# Adapter-RJ45-SignalHead.net
KiCad netlist of a schematic drawn in EAGLE
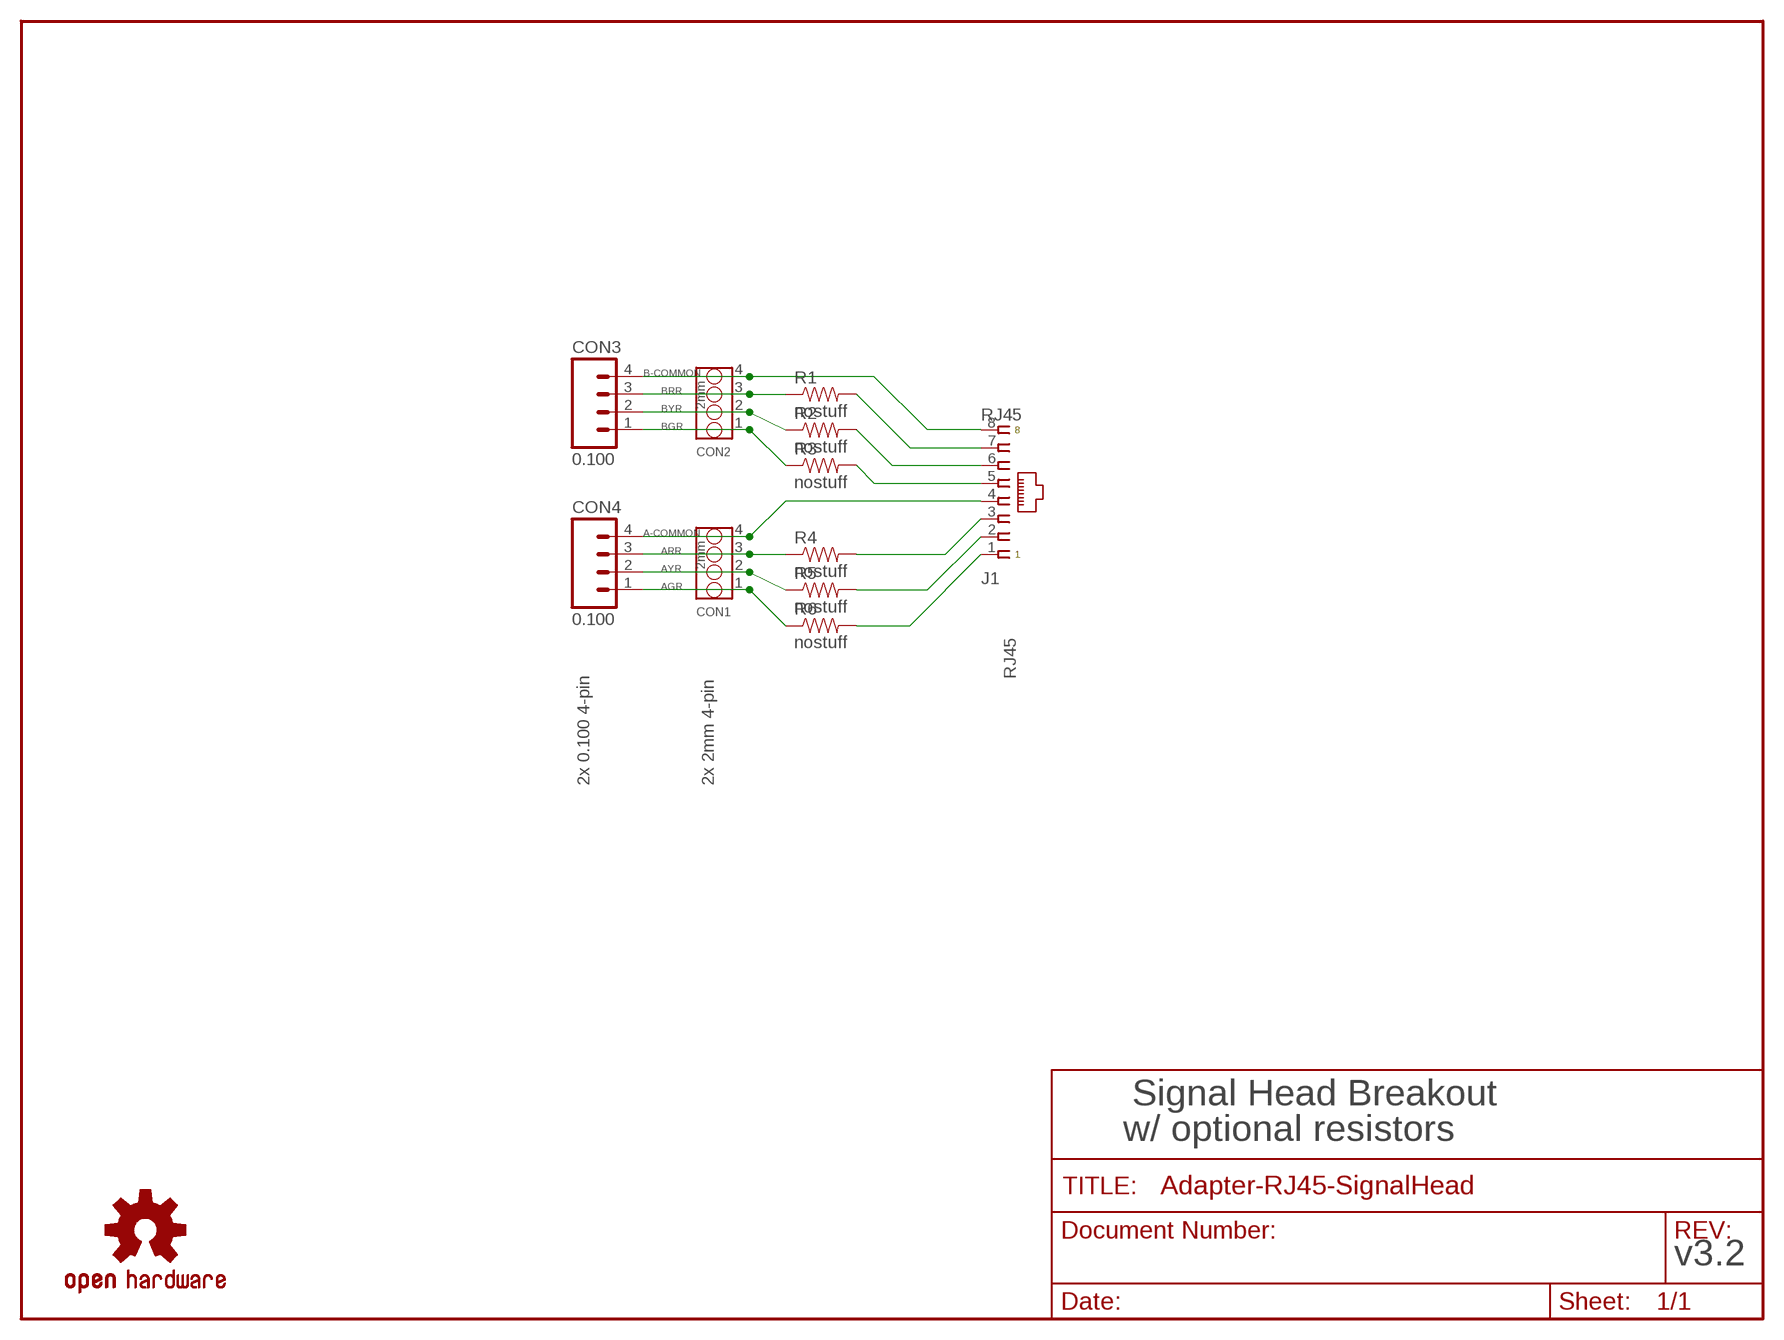
[diagram p0: schematic, sheet 1]

(export (version "E")
  (design (tool "Eeschema 10.0.6"))
  (components
    (comp (ref "CON1")
      (value "2mm")
      (footprint "eagle-import:4P-2.0")
      (libsource (lib "eagle-import") (part "CONNECTOR-GROVE-4P-2.0-3470130P1"))
    )
    (comp (ref "CON2")
      (value "2mm")
      (footprint "eagle-import:4P-2.0")
      (libsource (lib "eagle-import") (part "CONNECTOR-GROVE-4P-2.0-3470130P1"))
    )
    (comp (ref "CON3")
      (value "0.100")
      (footprint "eagle-import:1X04_LOCK")
      (libsource (lib "eagle-import") (part "CONNECTOR-M04LOCK"))
    )
    (comp (ref "CON4")
      (value "0.100")
      (footprint "eagle-import:1X04_LOCK")
      (libsource (lib "eagle-import") (part "CONNECTOR-M04LOCK"))
    )
    (comp (ref "J1")
      (value "RJ45")
      (footprint "eagle-import:RJ45-NO-SHIELD")
      (libsource (lib "eagle-import") (part "CONNECTOR-RJ45-FRONT"))
    )
    (comp (ref "R1")
      (value "nostuff")
      (footprint "eagle-import:CUT-R")
      (libsource (lib "eagle-import") (part "RPTH-R0"))
    )
    (comp (ref "R2")
      (value "nostuff")
      (footprint "eagle-import:CUT-R")
      (libsource (lib "eagle-import") (part "RPTH-R0"))
    )
    (comp (ref "R3")
      (value "nostuff")
      (footprint "eagle-import:CUT-R")
      (libsource (lib "eagle-import") (part "RPTH-R0"))
    )
    (comp (ref "R4")
      (value "nostuff")
      (footprint "eagle-import:CUT-R")
      (libsource (lib "eagle-import") (part "RPTH-R0"))
    )
    (comp (ref "R5")
      (value "nostuff")
      (footprint "eagle-import:CUT-R")
      (libsource (lib "eagle-import") (part "RPTH-R0"))
    )
    (comp (ref "R6")
      (value "nostuff")
      (footprint "eagle-import:CUT-R")
      (libsource (lib "eagle-import") (part "RPTH-R0"))
    )
    (comp (ref "U$1")
      (value "OSHW")
      (footprint "eagle-import:OSHW-LOGO-M")
      (libsource (lib "eagle-import") (part "DOC-OSHW-LOGO-M"))
    )
  )
  (nets
    (net (code "1") (name "/A-COMMON") (class "Default")
      (node (ref "CON1") (pin "4") (pinfunction "4_4") (pintype "bidirectional"))
      (node (ref "CON4") (pin "4") (pinfunction "4_4") (pintype "passive"))
      (node (ref "J1") (pin "4") (pinfunction "4_4") (pintype "passive"))
    )
    (net (code "2") (name "/AGR") (class "Default")
      (node (ref "CON1") (pin "1") (pinfunction "1_1") (pintype "bidirectional"))
      (node (ref "CON4") (pin "1") (pinfunction "1_1") (pintype "passive"))
      (node (ref "R6") (pin "P2") (pinfunction "1_P2") (pintype "passive"))
    )
    (net (code "3") (name "/ARR") (class "Default")
      (node (ref "CON1") (pin "3") (pinfunction "3_3") (pintype "bidirectional"))
      (node (ref "CON4") (pin "3") (pinfunction "3_3") (pintype "passive"))
      (node (ref "R4") (pin "P2") (pinfunction "1_P2") (pintype "passive"))
    )
    (net (code "4") (name "/AYR") (class "Default")
      (node (ref "CON1") (pin "2") (pinfunction "2_2") (pintype "bidirectional"))
      (node (ref "CON4") (pin "2") (pinfunction "2_2") (pintype "passive"))
      (node (ref "R5") (pin "P2") (pinfunction "1_P2") (pintype "passive"))
    )
    (net (code "5") (name "/B-COMMON") (class "Default")
      (node (ref "CON2") (pin "4") (pinfunction "4_4") (pintype "bidirectional"))
      (node (ref "CON3") (pin "4") (pinfunction "4_4") (pintype "passive"))
      (node (ref "J1") (pin "8") (pinfunction "8_8") (pintype "passive"))
    )
    (net (code "6") (name "/BGR") (class "Default")
      (node (ref "CON2") (pin "1") (pinfunction "1_1") (pintype "bidirectional"))
      (node (ref "CON3") (pin "1") (pinfunction "1_1") (pintype "passive"))
      (node (ref "R3") (pin "P2") (pinfunction "1_P2") (pintype "passive"))
    )
    (net (code "7") (name "/BRR") (class "Default")
      (node (ref "CON2") (pin "3") (pinfunction "3_3") (pintype "bidirectional"))
      (node (ref "CON3") (pin "3") (pinfunction "3_3") (pintype "passive"))
      (node (ref "R1") (pin "P2") (pinfunction "1_P2") (pintype "passive"))
    )
    (net (code "8") (name "/BYR") (class "Default")
      (node (ref "CON2") (pin "2") (pinfunction "2_2") (pintype "bidirectional"))
      (node (ref "CON3") (pin "2") (pinfunction "2_2") (pintype "passive"))
      (node (ref "R2") (pin "P2") (pinfunction "1_P2") (pintype "passive"))
    )
    (net (code "9") (name "Net-(R1-2)") (class "Default")
      (node (ref "J1") (pin "7") (pinfunction "7_7") (pintype "passive"))
      (node (ref "R1") (pin "P1") (pinfunction "2_P1") (pintype "passive"))
    )
    (net (code "10") (name "Net-(R2-2)") (class "Default")
      (node (ref "J1") (pin "6") (pinfunction "6_6") (pintype "passive"))
      (node (ref "R2") (pin "P1") (pinfunction "2_P1") (pintype "passive"))
    )
    (net (code "11") (name "Net-(R3-2)") (class "Default")
      (node (ref "J1") (pin "5") (pinfunction "5_5") (pintype "passive"))
      (node (ref "R3") (pin "P1") (pinfunction "2_P1") (pintype "passive"))
    )
    (net (code "12") (name "Net-(R4-2)") (class "Default")
      (node (ref "J1") (pin "3") (pinfunction "3_3") (pintype "passive"))
      (node (ref "R4") (pin "P1") (pinfunction "2_P1") (pintype "passive"))
    )
    (net (code "13") (name "Net-(R5-2)") (class "Default")
      (node (ref "J1") (pin "2") (pinfunction "2_2") (pintype "passive"))
      (node (ref "R5") (pin "P1") (pinfunction "2_P1") (pintype "passive"))
    )
    (net (code "14") (name "Net-(R6-2)") (class "Default")
      (node (ref "J1") (pin "1") (pinfunction "1_1") (pintype "passive"))
      (node (ref "R6") (pin "P1") (pinfunction "2_P1") (pintype "passive"))
    )
  )
)
